# Tracksoar_v1_bme_test.net
KiCad netlist of a schematic drawn in EAGLE
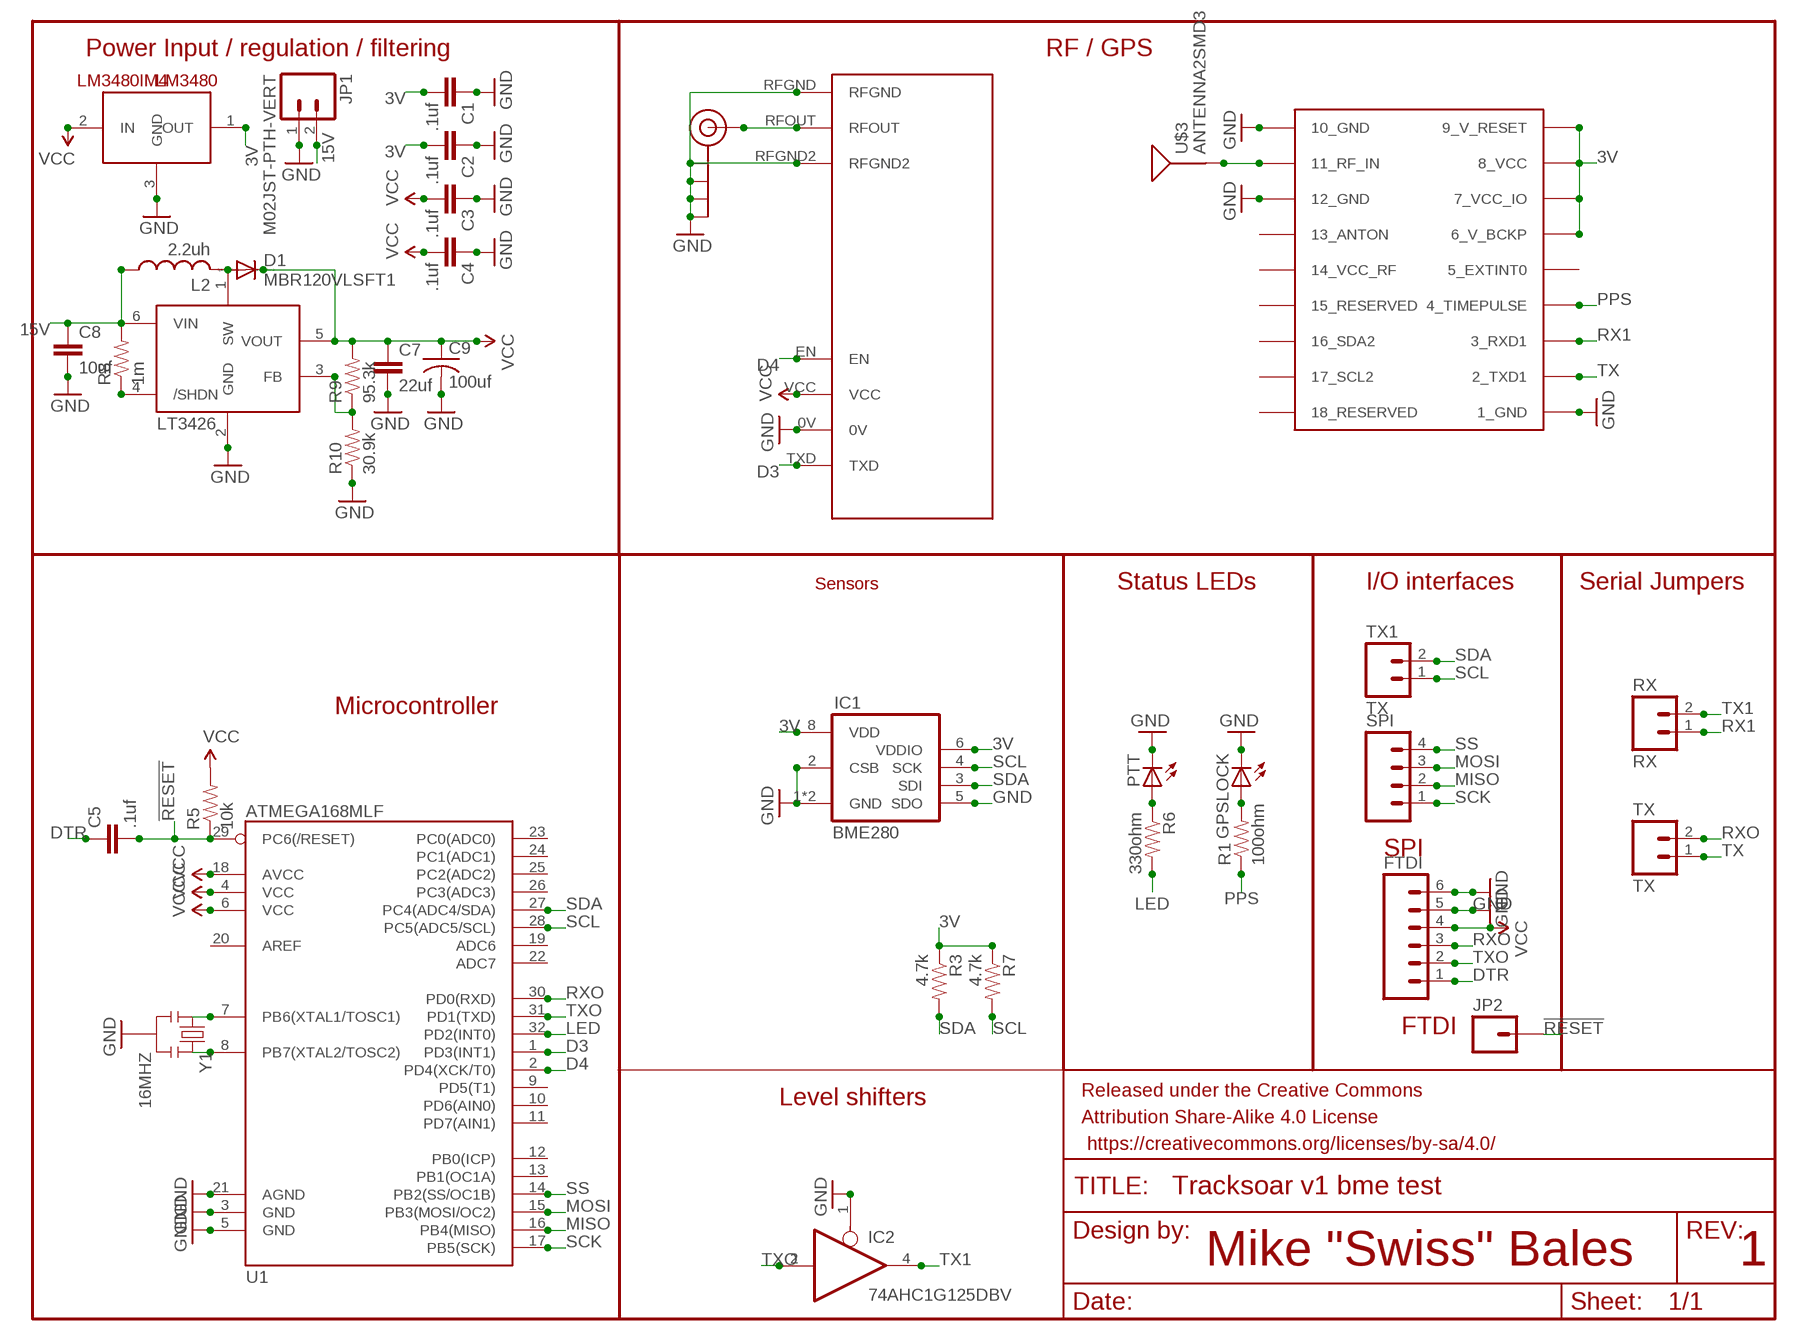
[diagram p0: schematic, sheet 1]

(export (version "E")
  (design (tool "Eeschema 10.0.6"))
  (components
    (comp (ref "C1")
      (value ".1uf")
      (footprint "eagle-import:0805")
      (libsource (lib "eagle-import") (part "CAP0805"))
    )
    (comp (ref "C2")
      (value ".1uf")
      (footprint "eagle-import:0805")
      (libsource (lib "eagle-import") (part "CAP0805"))
    )
    (comp (ref "C3")
      (value ".1uf")
      (footprint "eagle-import:0805")
      (libsource (lib "eagle-import") (part "CAP0805"))
    )
    (comp (ref "C4")
      (value ".1uf")
      (footprint "eagle-import:0805")
      (libsource (lib "eagle-import") (part "CAP0805"))
    )
    (comp (ref "C5")
      (value ".1uf")
      (footprint "eagle-import:0805")
      (libsource (lib "eagle-import") (part "CAP0805"))
    )
    (comp (ref "C7")
      (value "22uf")
      (footprint "eagle-import:0805")
      (libsource (lib "eagle-import") (part "CAP0805"))
    )
    (comp (ref "C8")
      (value "10uf")
      (footprint "eagle-import:0805")
      (libsource (lib "eagle-import") (part "CAP0805"))
    )
    (comp (ref "C9")
      (value "100uf")
      (footprint "eagle-import:C1206")
      (libsource (lib "eagle-import") (part "C-USC1206"))
    )
    (comp (ref "D1")
      (value "MBR120VLSFT1")
      (footprint "eagle-import:SOD123")
      (libsource (lib "eagle-import") (part "DIODE-SOD123"))
    )
    (comp (ref "FRAME1")
      (value "FRAME-LETTER")
      (footprint "eagle-import:CREATIVE_COMMONS")
      (libsource (lib "eagle-import") (part "FRAME-LETTER"))
    )
    (comp (ref "FTDI")
      (value "M06NO_SILK_FEMALE_PTH")
      (footprint "eagle-import:1X06_NO_SILK")
      (libsource (lib "eagle-import") (part "M06NO_SILK_FEMALE_PTH"))
    )
    (comp (ref "GPSLOCK")
      (value "LEDCHIP-LED0805")
      (footprint "eagle-import:CHIP-LED0805")
      (libsource (lib "eagle-import") (part "LEDCHIP-LED0805"))
    )
    (comp (ref "IC1")
      (value "BME280")
      (footprint "eagle-import:BME280")
      (libsource (lib "eagle-import") (part "BME280"))
    )
    (comp (ref "IC2")
      (value "74AHC1G125DBV")
      (footprint "eagle-import:SOT23-5")
      (libsource (lib "eagle-import") (part "741G125DBVAHC"))
    )
    (comp (ref "J$1")
      (value "SMA_EDGE")
      (footprint "eagle-import:SMA-EDGE")
      (libsource (lib "eagle-import") (part "SMA_EDGE"))
    )
    (comp (ref "JP1")
      (value "M02JST-PTH-VERT")
      (footprint "eagle-import:JST-2-PTH-VERT")
      (libsource (lib "eagle-import") (part "M02JST-PTH-VERT"))
    )
    (comp (ref "JP2")
      (value "M01PTH")
      (footprint "eagle-import:1X01")
      (libsource (lib "eagle-import") (part "M01PTH"))
    )
    (comp (ref "L2")
      (value "2.2uh")
      (footprint "eagle-import:L1812")
      (libsource (lib "eagle-import") (part "L-USL1812"))
    )
    (comp (ref "LM3480")
      (value "LM3480IM4")
      (footprint "eagle-import:SOT23-3")
      (libsource (lib "eagle-import") (part "LM3480IM4"))
    )
    (comp (ref "LT3426")
      (value "LT3426")
      (footprint "eagle-import:SOT23-6")
      (libsource (lib "eagle-import") (part "LT3426"))
    )
    (comp (ref "PTT")
      (value "LEDCHIP-LED0805")
      (footprint "eagle-import:CHIP-LED0805")
      (libsource (lib "eagle-import") (part "LEDCHIP-LED0805"))
    )
    (comp (ref "R1")
      (value "100ohm")
      (footprint "eagle-import:0805")
      (libsource (lib "eagle-import") (part "RESISTOR0805-RES"))
    )
    (comp (ref "R3")
      (value "4.7k")
      (footprint "eagle-import:0805")
      (libsource (lib "eagle-import") (part "RESISTOR0805-RES"))
    )
    (comp (ref "R5")
      (value "10k")
      (footprint "eagle-import:0805")
      (libsource (lib "eagle-import") (part "RESISTOR0805-RES"))
    )
    (comp (ref "R6")
      (value "330ohm")
      (footprint "eagle-import:0805")
      (libsource (lib "eagle-import") (part "RESISTOR0805-RES"))
    )
    (comp (ref "R7")
      (value "4.7k")
      (footprint "eagle-import:0805")
      (libsource (lib "eagle-import") (part "RESISTOR0805-RES"))
    )
    (comp (ref "R8")
      (value "1m")
      (footprint "eagle-import:0805")
      (libsource (lib "eagle-import") (part "RESISTOR0805-RES"))
    )
    (comp (ref "R9")
      (value "95.3k")
      (footprint "eagle-import:0805")
      (libsource (lib "eagle-import") (part "RESISTOR0805-RES"))
    )
    (comp (ref "R10")
      (value "30.9k")
      (footprint "eagle-import:0805")
      (libsource (lib "eagle-import") (part "RESISTOR0805-RES"))
    )
    (comp (ref "RX")
      (value "RX")
      (footprint "eagle-import:JST-2-PTH-VERT")
      (libsource (lib "eagle-import") (part "M02JST-PTH-VERT"))
    )
    (comp (ref "SPI")
      (value "M04JST-PTH-VERT")
      (footprint "eagle-import:JST-4-PTH-VERT")
      (libsource (lib "eagle-import") (part "M04JST-PTH-VERT"))
    )
    (comp (ref "TX")
      (value "TX")
      (footprint "eagle-import:JST-2-PTH-VERT")
      (libsource (lib "eagle-import") (part "M02JST-PTH-VERT"))
    )
    (comp (ref "TX1")
      (value "TX")
      (footprint "eagle-import:JST-2-PTH-VERT")
      (libsource (lib "eagle-import") (part "M02JST-PTH-VERT"))
    )
    (comp (ref "U$1")
      (value "UBLOX_MAX")
      (footprint "eagle-import:UBLOX_MAX")
      (libsource (lib "eagle-import") (part "UBLOX_MAX"))
    )
    (comp (ref "U$2")
      (value "RADIOMETRIX-HX1")
      (footprint "eagle-import:RADIOMETRIX-HX1")
      (libsource (lib "eagle-import") (part "RADIOMETRIX-HX1"))
    )
    (comp (ref "U$3")
      (value "ANTENNA2SMD3")
      (footprint "eagle-import:ANTENNA-CHIP4")
      (libsource (lib "eagle-import") (part "ANTENNA2SMD3"))
    )
    (comp (ref "U1")
      (value "ATMEGA168MLF")
      (footprint "eagle-import:MLF32")
      (libsource (lib "eagle-import") (part "ATMEGA168MLF"))
    )
    (comp (ref "Y1")
      (value "16MHZ")
      (footprint "eagle-import:RESONATOR-SMD")
      (libsource (lib "eagle-import") (part "RESONATOR16MHZ"))
    )
  )
  (nets
    (net (code "1") (name "/3V") (class "Default")
      (node (ref "C1") (pin "2") (pinfunction "2_2") (pintype "passive"))
      (node (ref "C2") (pin "2") (pinfunction "2_2") (pintype "passive"))
      (node (ref "IC1") (pin "6") (pinfunction "VDDIO_6") (pintype "power_in"))
      (node (ref "IC1") (pin "8") (pinfunction "VDD_8") (pintype "power_in"))
      (node (ref "LM3480") (pin "1") (pinfunction "OUT_1") (pintype "bidirectional"))
      (node (ref "R3") (pin "1") (pinfunction "1_1") (pintype "passive"))
      (node (ref "R7") (pin "1") (pinfunction "1_1") (pintype "passive"))
      (node (ref "U$1") (pin "6_V_BCKP") (pinfunction "6_V_BCKP_6_V_BCKP") (pintype "bidirectional"))
      (node (ref "U$1") (pin "7_VCC_IO") (pinfunction "7_VCC_IO_7_VCC_IO") (pintype "power_in"))
      (node (ref "U$1") (pin "8_VCC") (pinfunction "8_VCC_8_VCC") (pintype "power_in"))
      (node (ref "U$1") (pin "9_V_RESET") (pinfunction "9_V_RESET_9_V_RESET") (pintype "power_in"))
    )
    (net (code "2") (name "/15V") (class "Default")
      (node (ref "C8") (pin "1") (pinfunction "1_1") (pintype "passive"))
      (node (ref "JP1") (pin "2") (pinfunction "2_2") (pintype "passive"))
      (node (ref "L2") (pin "1") (pinfunction "1_1") (pintype "passive"))
      (node (ref "LT3426") (pin "6") (pinfunction "VIN_6") (pintype "input"))
      (node (ref "R8") (pin "2") (pinfunction "2_2") (pintype "passive"))
    )
    (net (code "3") (name "/D3") (class "Default")
      (node (ref "U$2") (pin "TXD") (pinfunction "TXD_TXD") (pintype "bidirectional"))
      (node (ref "U1") (pin "1") (pinfunction "PD3(INT1)_1") (pintype "bidirectional"))
    )
    (net (code "4") (name "/D4") (class "Default")
      (node (ref "U$2") (pin "EN") (pinfunction "EN_EN") (pintype "bidirectional"))
      (node (ref "U1") (pin "2") (pinfunction "PD4(XCK/T0)_2") (pintype "bidirectional"))
    )
    (net (code "5") (name "/DTR") (class "Default")
      (node (ref "C5") (pin "1") (pinfunction "1_1") (pintype "passive"))
      (node (ref "FTDI") (pin "1") (pinfunction "1_1") (pintype "passive"))
    )
    (net (code "6") (name "/LED") (class "Default")
      (node (ref "R6") (pin "2") (pinfunction "2_2") (pintype "passive"))
      (node (ref "U1") (pin "32") (pinfunction "PD2(INT0)_32") (pintype "bidirectional"))
    )
    (net (code "7") (name "/MISO") (class "Default")
      (node (ref "SPI") (pin "2") (pinfunction "2_2") (pintype "passive"))
      (node (ref "U1") (pin "16") (pinfunction "PB4(MISO)_16") (pintype "bidirectional"))
    )
    (net (code "8") (name "/MOSI") (class "Default")
      (node (ref "SPI") (pin "3") (pinfunction "3_3") (pintype "passive"))
      (node (ref "U1") (pin "15") (pinfunction "PB3(MOSI/OC2)_15") (pintype "bidirectional"))
    )
    (net (code "9") (name "/PPS") (class "Default")
      (node (ref "R1") (pin "1") (pinfunction "1_1") (pintype "passive"))
      (node (ref "U$1") (pin "4_TIMEPULSE") (pinfunction "4_TIMEPULSE_4_TIMEPULSE") (pintype "bidirectional"))
    )
    (net (code "10") (name "/RX1") (class "Default")
      (node (ref "RX") (pin "1") (pinfunction "1_1") (pintype "passive"))
      (node (ref "U$1") (pin "3_RXD1") (pinfunction "3_RXD1_3_RXD1") (pintype "bidirectional"))
    )
    (net (code "11") (name "/RXO") (class "Default")
      (node (ref "FTDI") (pin "3") (pinfunction "3_3") (pintype "passive"))
      (node (ref "TX") (pin "2") (pinfunction "2_2") (pintype "passive"))
      (node (ref "U1") (pin "30") (pinfunction "PD0(RXD)_30") (pintype "bidirectional"))
    )
    (net (code "12") (name "/SCK") (class "Default")
      (node (ref "SPI") (pin "1") (pinfunction "1_1") (pintype "passive"))
      (node (ref "U1") (pin "17") (pinfunction "PB5(SCK)_17") (pintype "bidirectional"))
    )
    (net (code "13") (name "/SCL") (class "Default")
      (node (ref "IC1") (pin "4") (pinfunction "SCK_4") (pintype "bidirectional"))
      (node (ref "R7") (pin "2") (pinfunction "2_2") (pintype "passive"))
      (node (ref "TX1") (pin "1") (pinfunction "1_1") (pintype "passive"))
      (node (ref "U1") (pin "28") (pinfunction "PC5(ADC5/SCL)_28") (pintype "bidirectional"))
    )
    (net (code "14") (name "/SDA") (class "Default")
      (node (ref "IC1") (pin "3") (pinfunction "SDI_3") (pintype "bidirectional"))
      (node (ref "R3") (pin "2") (pinfunction "2_2") (pintype "passive"))
      (node (ref "TX1") (pin "2") (pinfunction "2_2") (pintype "passive"))
      (node (ref "U1") (pin "27") (pinfunction "PC4(ADC4/SDA)_27") (pintype "bidirectional"))
    )
    (net (code "15") (name "/SS") (class "Default")
      (node (ref "SPI") (pin "4") (pinfunction "4_4") (pintype "passive"))
      (node (ref "U1") (pin "14") (pinfunction "PB2(SS/OC1B)_14") (pintype "bidirectional"))
    )
    (net (code "16") (name "/TX") (class "Default")
      (node (ref "TX") (pin "1") (pinfunction "1_1") (pintype "passive"))
      (node (ref "U$1") (pin "2_TXD1") (pinfunction "2_TXD1_2_TXD1") (pintype "bidirectional"))
    )
    (net (code "17") (name "/TX1") (class "Default")
      (node (ref "IC2") (pin "4") (pinfunction "O_4") (pintype "tri_state"))
      (node (ref "RX") (pin "2") (pinfunction "2_2") (pintype "passive"))
    )
    (net (code "18") (name "/TXO") (class "Default")
      (node (ref "FTDI") (pin "2") (pinfunction "2_2") (pintype "passive"))
      (node (ref "IC2") (pin "2") (pinfunction "I_2") (pintype "input"))
      (node (ref "U1") (pin "31") (pinfunction "PD1(TXD)_31") (pintype "bidirectional"))
    )
    (net (code "19") (name "/~{RESET}") (class "Default")
      (node (ref "C5") (pin "2") (pinfunction "2_2") (pintype "passive"))
      (node (ref "JP2") (pin "1") (pinfunction "1_1") (pintype "passive"))
      (node (ref "R5") (pin "1") (pinfunction "1_1") (pintype "passive"))
      (node (ref "U1") (pin "29") (pinfunction "PC6(/RESET)_29") (pintype "bidirectional"))
    )
    (net (code "20") (name "GND") (class "Default")
      (node (ref "C1") (pin "1") (pinfunction "1_1") (pintype "passive"))
      (node (ref "C2") (pin "1") (pinfunction "1_1") (pintype "passive"))
      (node (ref "C3") (pin "1") (pinfunction "1_1") (pintype "passive"))
      (node (ref "C4") (pin "1") (pinfunction "1_1") (pintype "passive"))
      (node (ref "C7") (pin "2") (pinfunction "2_2") (pintype "passive"))
      (node (ref "C8") (pin "2") (pinfunction "2_2") (pintype "passive"))
      (node (ref "C9") (pin "2") (pinfunction "2_2") (pintype "passive"))
      (node (ref "FTDI") (pin "5") (pinfunction "5_5") (pintype "passive"))
      (node (ref "FTDI") (pin "6") (pinfunction "6_6") (pintype "passive"))
      (node (ref "GPSLOCK") (pin "C") (pinfunction "C_C") (pintype "passive"))
      (node (ref "IC1") (pin "1") (pinfunction "GND_1") (pintype "power_in"))
      (node (ref "IC1") (pin "2") (pinfunction "CSB_2") (pintype "input"))
      (node (ref "IC1") (pin "5") (pinfunction "SDO_5") (pintype "input"))
      (node (ref "IC1") (pin "7") (pinfunction "GND_7") (pintype "power_in"))
      (node (ref "IC2") (pin "1") (pinfunction "OE_1") (pintype "input"))
      (node (ref "J$1") (pin "GND@0") (pinfunction "GND_GND@0") (pintype "bidirectional"))
      (node (ref "J$1") (pin "GND@1") (pinfunction "GND_GND@1") (pintype "bidirectional"))
      (node (ref "J$1") (pin "GND@2") (pinfunction "GND_GND@2") (pintype "bidirectional"))
      (node (ref "J$1") (pin "GND@3") (pinfunction "GND_GND@3") (pintype "bidirectional"))
      (node (ref "JP1") (pin "1") (pinfunction "1_1") (pintype "passive"))
      (node (ref "LM3480") (pin "3") (pinfunction "GND_3") (pintype "bidirectional"))
      (node (ref "LT3426") (pin "2") (pinfunction "GND_2") (pintype "power_in"))
      (node (ref "PTT") (pin "C") (pinfunction "C_C") (pintype "passive"))
      (node (ref "R10") (pin "1") (pinfunction "1_1") (pintype "passive"))
      (node (ref "U$1") (pin "10_GND") (pinfunction "10_GND_10_GND") (pintype "power_in"))
      (node (ref "U$1") (pin "12_GND") (pinfunction "12_GND_12_GND") (pintype "power_in"))
      (node (ref "U$1") (pin "1_GND") (pinfunction "1_GND_1_GND") (pintype "power_in"))
      (node (ref "U$2") (pin "0V") (pinfunction "0V_0V") (pintype "bidirectional"))
      (node (ref "U$2") (pin "RFGND") (pinfunction "RFGND_RFGND") (pintype "bidirectional"))
      (node (ref "U$2") (pin "RFGND2") (pinfunction "RFGND2_RFGND2") (pintype "bidirectional"))
      (node (ref "U1") (pin "21") (pinfunction "AGND_21") (pintype "bidirectional"))
      (node (ref "U1") (pin "3") (pinfunction "GND_3") (pintype "bidirectional"))
      (node (ref "U1") (pin "5") (pinfunction "GND_5") (pintype "bidirectional"))
      (node (ref "Y1") (pin "2") (pinfunction "2_2") (pintype "passive"))
    )
    (net (code "21") (name "Net-(GPSLOCK-PadA)") (class "Default")
      (node (ref "GPSLOCK") (pin "A") (pinfunction "A_A") (pintype "passive"))
      (node (ref "R1") (pin "2") (pinfunction "2_2") (pintype "passive"))
    )
    (net (code "22") (name "Net-(J$1-SIGNAL)") (class "Default")
      (node (ref "J$1") (pin "SIG") (pinfunction "SIGNAL_SIG") (pintype "bidirectional"))
      (node (ref "U$2") (pin "RFOUT") (pinfunction "RFOUT_RFOUT") (pintype "bidirectional"))
    )
    (net (code "23") (name "Net-(LT3426-FB)") (class "Default")
      (node (ref "LT3426") (pin "3") (pinfunction "FB_3") (pintype "input"))
      (node (ref "R10") (pin "2") (pinfunction "2_2") (pintype "passive"))
      (node (ref "R9") (pin "1") (pinfunction "1_1") (pintype "passive"))
    )
    (net (code "24") (name "Net-(LT3426-SW)") (class "Default")
      (node (ref "D1") (pin "A") (pinfunction "A_A") (pintype "passive"))
      (node (ref "L2") (pin "2") (pinfunction "2_2") (pintype "passive"))
      (node (ref "LT3426") (pin "1") (pinfunction "SW_1") (pintype "output"))
    )
    (net (code "25") (name "Net-(LT3426-{slash}SHDN)") (class "Default")
      (node (ref "LT3426") (pin "4") (pinfunction "/SHDN_4") (pintype "input"))
      (node (ref "R8") (pin "1") (pinfunction "1_1") (pintype "passive"))
    )
    (net (code "26") (name "Net-(PTT-PadA)") (class "Default")
      (node (ref "PTT") (pin "A") (pinfunction "A_A") (pintype "passive"))
      (node (ref "R6") (pin "1") (pinfunction "1_1") (pintype "passive"))
    )
    (net (code "27") (name "Net-(U$3-SIGNAL)") (class "Default")
      (node (ref "U$1") (pin "11_RF_IN") (pinfunction "11_RF_IN_11_RF_IN") (pintype "bidirectional"))
      (node (ref "U$3") (pin "SIG") (pinfunction "SIGNAL_SIG") (pintype "bidirectional"))
    )
    (net (code "28") (name "Net-(U1-PB6(XTAL1{slash}TOSC1))") (class "Default")
      (node (ref "U1") (pin "7") (pinfunction "PB6(XTAL1/TOSC1)_7") (pintype "bidirectional"))
      (node (ref "Y1") (pin "1") (pinfunction "1_1") (pintype "passive"))
    )
    (net (code "29") (name "Net-(U1-PB7(XTAL2{slash}TOSC2))") (class "Default")
      (node (ref "U1") (pin "8") (pinfunction "PB7(XTAL2/TOSC2)_8") (pintype "bidirectional"))
      (node (ref "Y1") (pin "3") (pinfunction "3_3") (pintype "passive"))
    )
    (net (code "30") (name "VCC") (class "Default")
      (node (ref "C3") (pin "2") (pinfunction "2_2") (pintype "passive"))
      (node (ref "C4") (pin "2") (pinfunction "2_2") (pintype "passive"))
      (node (ref "C7") (pin "1") (pinfunction "1_1") (pintype "passive"))
      (node (ref "C9") (pin "1") (pinfunction "1_1") (pintype "passive"))
      (node (ref "D1") (pin "C") (pinfunction "C_C") (pintype "passive"))
      (node (ref "FTDI") (pin "4") (pinfunction "4_4") (pintype "passive"))
      (node (ref "LM3480") (pin "2") (pinfunction "IN_2") (pintype "bidirectional"))
      (node (ref "LT3426") (pin "5") (pinfunction "VOUT_5") (pintype "output"))
      (node (ref "R5") (pin "2") (pinfunction "2_2") (pintype "passive"))
      (node (ref "R9") (pin "2") (pinfunction "2_2") (pintype "passive"))
      (node (ref "U$2") (pin "VCC") (pinfunction "VCC_VCC") (pintype "bidirectional"))
      (node (ref "U1") (pin "18") (pinfunction "AVCC_18") (pintype "bidirectional"))
      (node (ref "U1") (pin "4") (pinfunction "VCC_4") (pintype "bidirectional"))
      (node (ref "U1") (pin "6") (pinfunction "VCC_6") (pintype "bidirectional"))
    )
    (net (code "31") (name "unconnected-(U$1-Pad5_EXTINT0)") (class "Default")
      (node (ref "U$1") (pin "5_EXTINT0") (pinfunction "5_EXTINT0_5_EXTINT0") (pintype "bidirectional"))
    )
    (net (code "32") (name "unconnected-(U$1-Pad13_ANTON)") (class "Default")
      (node (ref "U$1") (pin "13_ANTON") (pinfunction "13_ANTON_13_ANTON") (pintype "bidirectional"))
    )
    (net (code "33") (name "unconnected-(U$1-Pad14_VCC_RF)") (class "Default")
      (node (ref "U$1") (pin "14_VCC_RF") (pinfunction "14_VCC_RF_14_VCC_RF") (pintype "bidirectional"))
    )
    (net (code "34") (name "unconnected-(U$1-Pad15_RESERVED)") (class "Default")
      (node (ref "U$1") (pin "15_RESERVED") (pinfunction "15_RESERVED_15_RESERVED") (pintype "bidirectional"))
    )
    (net (code "35") (name "unconnected-(U$1-Pad16_SDA2)") (class "Default")
      (node (ref "U$1") (pin "16_SDA2") (pinfunction "16_SDA2_16_SDA2") (pintype "bidirectional"))
    )
    (net (code "36") (name "unconnected-(U$1-Pad17_SCL2)") (class "Default")
      (node (ref "U$1") (pin "17_SCL2") (pinfunction "17_SCL2_17_SCL2") (pintype "bidirectional"))
    )
    (net (code "37") (name "unconnected-(U$1-Pad18_RESERVED)") (class "Default")
      (node (ref "U$1") (pin "18_RESERVED") (pinfunction "18_RESERVED_18_RESERVED") (pintype "bidirectional"))
    )
    (net (code "38") (name "unconnected-(U1-ADC6-Pad19)") (class "Default")
      (node (ref "U1") (pin "19") (pinfunction "ADC6_19") (pintype "bidirectional"))
    )
    (net (code "39") (name "unconnected-(U1-ADC7-Pad22)") (class "Default")
      (node (ref "U1") (pin "22") (pinfunction "ADC7_22") (pintype "bidirectional"))
    )
    (net (code "40") (name "unconnected-(U1-AREF-Pad20)") (class "Default")
      (node (ref "U1") (pin "20") (pinfunction "AREF_20") (pintype "bidirectional"))
    )
    (net (code "41") (name "unconnected-(U1-PB0(ICP)-Pad12)") (class "Default")
      (node (ref "U1") (pin "12") (pinfunction "PB0(ICP)_12") (pintype "bidirectional"))
    )
    (net (code "42") (name "unconnected-(U1-PB1(OC1A)-Pad13)") (class "Default")
      (node (ref "U1") (pin "13") (pinfunction "PB1(OC1A)_13") (pintype "bidirectional"))
    )
    (net (code "43") (name "unconnected-(U1-PC0(ADC0)-Pad23)") (class "Default")
      (node (ref "U1") (pin "23") (pinfunction "PC0(ADC0)_23") (pintype "bidirectional"))
    )
    (net (code "44") (name "unconnected-(U1-PC1(ADC1)-Pad24)") (class "Default")
      (node (ref "U1") (pin "24") (pinfunction "PC1(ADC1)_24") (pintype "bidirectional"))
    )
    (net (code "45") (name "unconnected-(U1-PC2(ADC2)-Pad25)") (class "Default")
      (node (ref "U1") (pin "25") (pinfunction "PC2(ADC2)_25") (pintype "bidirectional"))
    )
    (net (code "46") (name "unconnected-(U1-PC3(ADC3)-Pad26)") (class "Default")
      (node (ref "U1") (pin "26") (pinfunction "PC3(ADC3)_26") (pintype "bidirectional"))
    )
    (net (code "47") (name "unconnected-(U1-PD5(T1)-Pad9)") (class "Default")
      (node (ref "U1") (pin "9") (pinfunction "PD5(T1)_9") (pintype "bidirectional"))
    )
    (net (code "48") (name "unconnected-(U1-PD6(AIN0)-Pad10)") (class "Default")
      (node (ref "U1") (pin "10") (pinfunction "PD6(AIN0)_10") (pintype "bidirectional"))
    )
    (net (code "49") (name "unconnected-(U1-PD7(AIN1)-Pad11)") (class "Default")
      (node (ref "U1") (pin "11") (pinfunction "PD7(AIN1)_11") (pintype "bidirectional"))
    )
  )
)
